# ViseraFPGA_v1_0.net
KiCad netlist of a schematic drawn in EAGLE
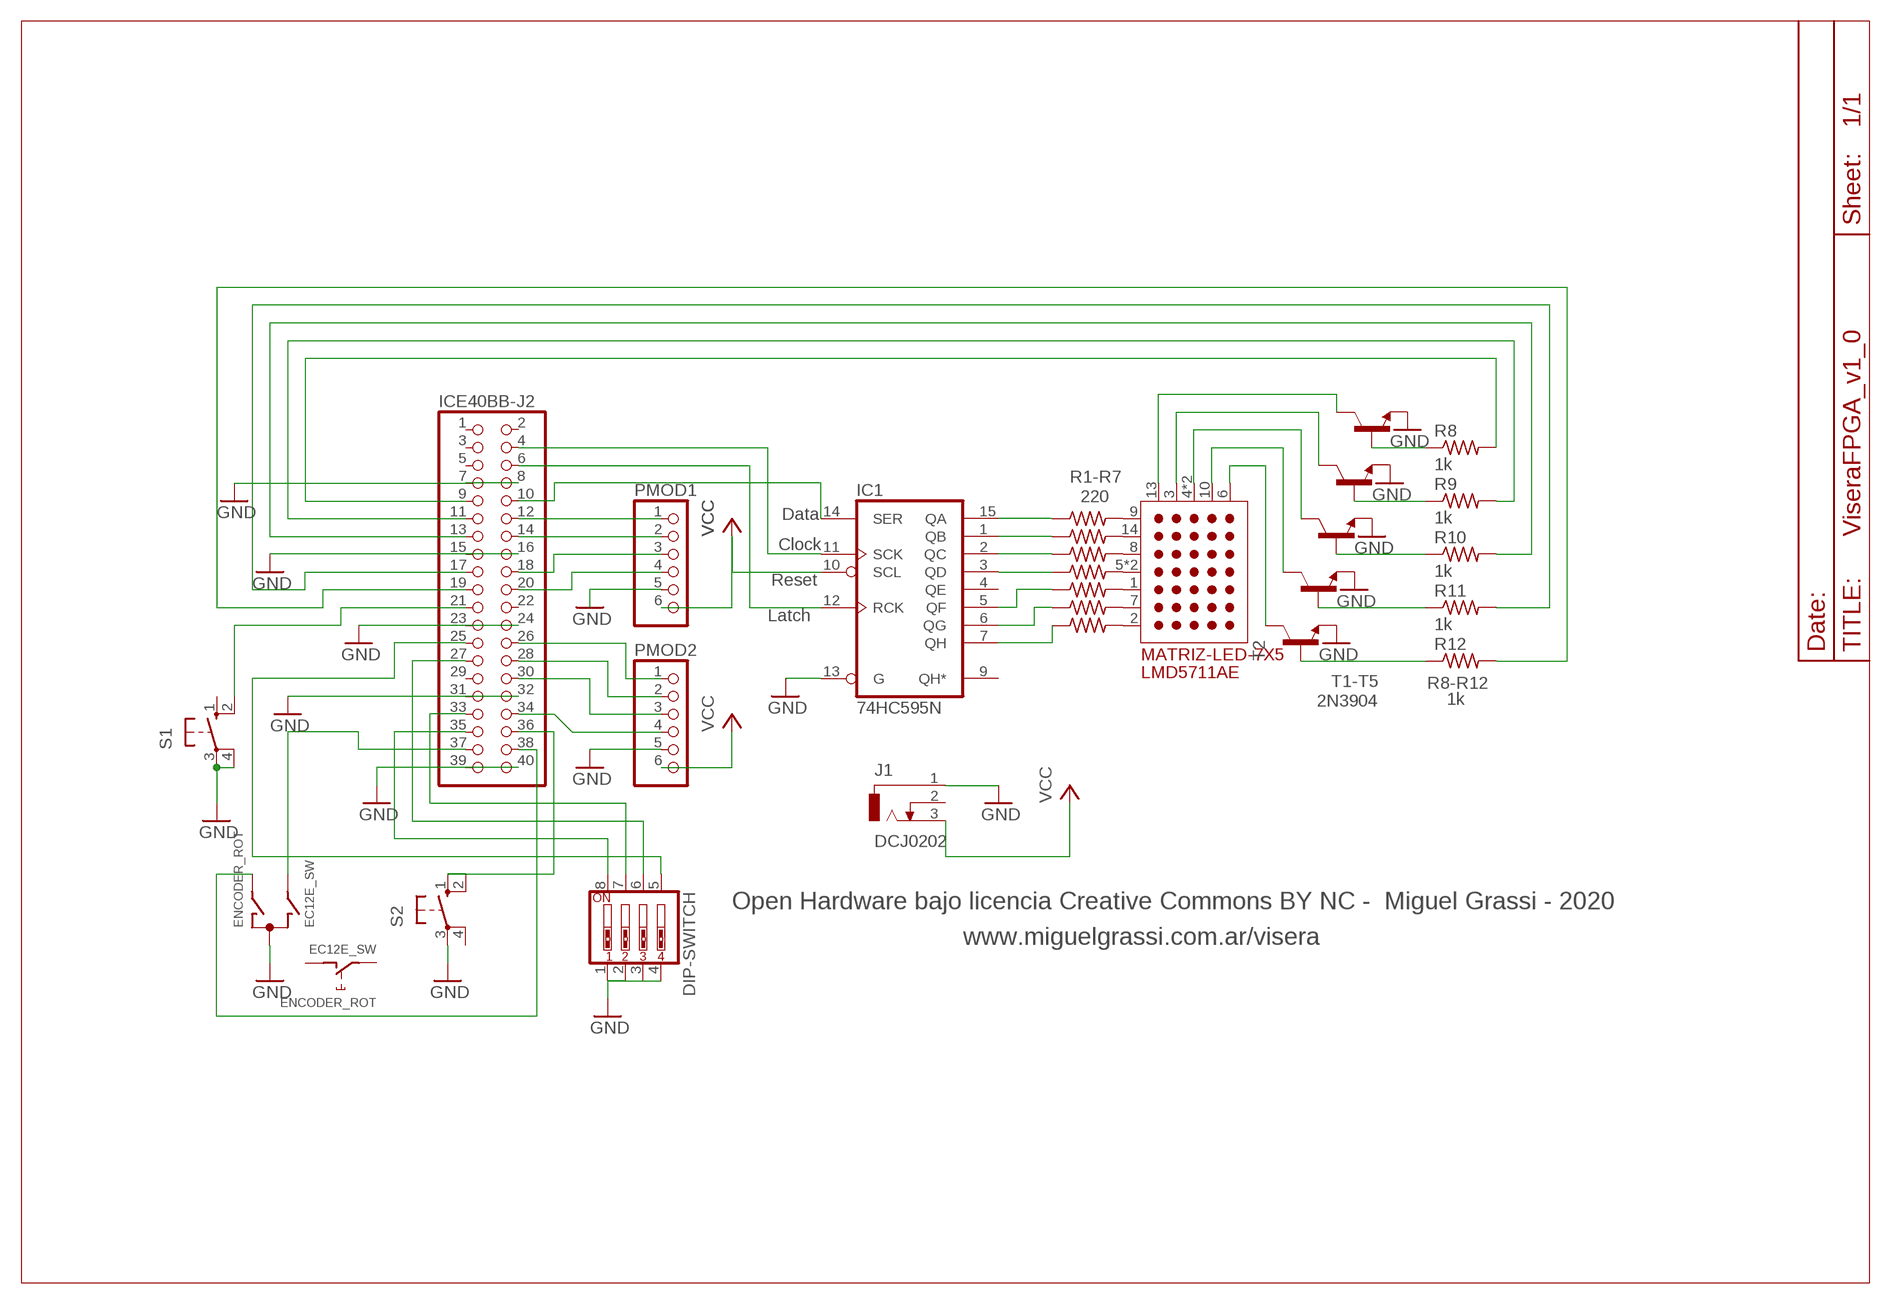
[diagram p0: schematic, sheet 1]

(export (version "E")
  (design (tool "Eeschema 10.0.6"))
  (components
    (comp (ref "DIP-SWITCH")
      (value "SW_DIP-4")
      (footprint "eagle-import:EDG-04")
      (libsource (lib "eagle-import") (part "SW_DIP-4"))
    )
    (comp (ref "ENCODER_ROT")
      (value "EC12E_SW")
      (footprint "eagle-import:ALPS_EC12E_SW")
      (fields (field (name "MPN") "EC12E2424407"))
      (libsource (lib "eagle-import") (part "EC12E_SW"))
    )
    (comp (ref "IC1")
      (value "74HC595N")
      (footprint "eagle-import:DIL16")
      (libsource (lib "eagle-import") (part "74595NHC"))
    )
    (comp (ref "ICE40BB-J2")
      (value "PINHD-2X20")
      (footprint "eagle-import:2X20")
      (libsource (lib "eagle-import") (part "PINHD-2X20"))
    )
    (comp (ref "J1")
      (value "DCJ0202")
      (footprint "eagle-import:DCJ0202")
      (libsource (lib "eagle-import") (part "DCJ0202"))
    )
    (comp (ref "MATRIZ-LED-7X5")
      (value "LMD5711AE")
      (footprint "eagle-import:LMD5711AE")
      (libsource (lib "eagle-import") (part "LMD5711AE"))
    )
    (comp (ref "PMOD1")
      (value "PINHD-1X6")
      (footprint "eagle-import:1X06")
      (libsource (lib "eagle-import") (part "PINHD-1X6"))
    )
    (comp (ref "PMOD2")
      (value "PINHD-1X6")
      (footprint "eagle-import:1X06")
      (libsource (lib "eagle-import") (part "PINHD-1X6"))
    )
    (comp (ref "R1")
      (value "220")
      (footprint "eagle-import:0207_7")
      (libsource (lib "eagle-import") (part "R-US_0207/7"))
    )
    (comp (ref "R2")
      (value "220")
      (footprint "eagle-import:0207_7")
      (libsource (lib "eagle-import") (part "R-US_0207/7"))
    )
    (comp (ref "R3")
      (value "220")
      (footprint "eagle-import:0207_7")
      (libsource (lib "eagle-import") (part "R-US_0207/7"))
    )
    (comp (ref "R4")
      (value "220")
      (footprint "eagle-import:0207_7")
      (libsource (lib "eagle-import") (part "R-US_0207/7"))
    )
    (comp (ref "R5")
      (value "220")
      (footprint "eagle-import:0207_7")
      (libsource (lib "eagle-import") (part "R-US_0207/7"))
    )
    (comp (ref "R6")
      (value "220")
      (footprint "eagle-import:0207_7")
      (libsource (lib "eagle-import") (part "R-US_0207/7"))
    )
    (comp (ref "R7")
      (value "220")
      (footprint "eagle-import:0207_7")
      (libsource (lib "eagle-import") (part "R-US_0207/7"))
    )
    (comp (ref "R8")
      (value "1k")
      (footprint "eagle-import:0207_7")
      (libsource (lib "eagle-import") (part "R-US_0207/7"))
    )
    (comp (ref "R9")
      (value "1k")
      (footprint "eagle-import:0207_7")
      (libsource (lib "eagle-import") (part "R-US_0207/7"))
    )
    (comp (ref "R10")
      (value "1k")
      (footprint "eagle-import:0207_7")
      (libsource (lib "eagle-import") (part "R-US_0207/7"))
    )
    (comp (ref "R11")
      (value "1k")
      (footprint "eagle-import:0207_7")
      (libsource (lib "eagle-import") (part "R-US_0207/7"))
    )
    (comp (ref "R12")
      (value "1k")
      (footprint "eagle-import:0207_7")
      (libsource (lib "eagle-import") (part "R-US_0207/7"))
    )
    (comp (ref "S1")
      (value "10-XX")
      (footprint "eagle-import:B3F-10XX")
      (fields (field (name "MPN") "B3F-1000"))
      (libsource (lib "eagle-import") (part "10-XX"))
    )
    (comp (ref "S2")
      (value "10-XX")
      (footprint "eagle-import:B3F-10XX")
      (fields (field (name "MPN") "B3F-1000"))
      (libsource (lib "eagle-import") (part "10-XX"))
    )
    (comp (ref "T1")
      (value "2N3904")
      (footprint "eagle-import:TO92")
      (libsource (lib "eagle-import") (part "2N3904"))
    )
    (comp (ref "T2")
      (value "2N3904")
      (footprint "eagle-import:TO92")
      (libsource (lib "eagle-import") (part "2N3904"))
    )
    (comp (ref "T3")
      (value "2N3904")
      (footprint "eagle-import:TO92")
      (libsource (lib "eagle-import") (part "2N3904"))
    )
    (comp (ref "T4")
      (value "2N3904")
      (footprint "eagle-import:TO92")
      (libsource (lib "eagle-import") (part "2N3904"))
    )
    (comp (ref "T5")
      (value "2N3904")
      (footprint "eagle-import:TO92")
      (libsource (lib "eagle-import") (part "2N3904"))
    )
  )
  (nets
    (net (code "1") (name "GND") (class "Default")
      (node (ref "DIP-SWITCH") (pin "1") (pinfunction "1_1") (pintype "passive"))
      (node (ref "DIP-SWITCH") (pin "2") (pinfunction "2_2") (pintype "passive"))
      (node (ref "DIP-SWITCH") (pin "3") (pinfunction "3_3") (pintype "passive"))
      (node (ref "DIP-SWITCH") (pin "4") (pinfunction "4_4") (pintype "passive"))
      (node (ref "ENCODER_ROT") (pin "C") (pinfunction "C_C") (pintype "passive"))
      (node (ref "IC1") (pin "13") (pinfunction "G_13") (pintype "input"))
      (node (ref "ICE40BB-J2") (pin "15") (pinfunction "15_15") (pintype "passive"))
      (node (ref "ICE40BB-J2") (pin "16") (pinfunction "16_16") (pintype "passive"))
      (node (ref "ICE40BB-J2") (pin "23") (pinfunction "23_23") (pintype "passive"))
      (node (ref "ICE40BB-J2") (pin "24") (pinfunction "24_24") (pintype "passive"))
      (node (ref "ICE40BB-J2") (pin "31") (pinfunction "31_31") (pintype "passive"))
      (node (ref "ICE40BB-J2") (pin "32") (pinfunction "32_32") (pintype "passive"))
      (node (ref "ICE40BB-J2") (pin "39") (pinfunction "39_39") (pintype "passive"))
      (node (ref "ICE40BB-J2") (pin "40") (pinfunction "40_40") (pintype "passive"))
      (node (ref "ICE40BB-J2") (pin "7") (pinfunction "7_7") (pintype "passive"))
      (node (ref "ICE40BB-J2") (pin "8") (pinfunction "8_8") (pintype "passive"))
      (node (ref "J1") (pin "1") (pinfunction "1_1") (pintype "passive"))
      (node (ref "PMOD1") (pin "5") (pinfunction "5_5") (pintype "passive"))
      (node (ref "PMOD2") (pin "5") (pinfunction "5_5") (pintype "passive"))
      (node (ref "S1") (pin "3") (pinfunction "P_3") (pintype "passive"))
      (node (ref "S1") (pin "4") (pinfunction "P1_4") (pintype "passive"))
      (node (ref "S2") (pin "3") (pinfunction "P_3") (pintype "passive"))
      (node (ref "T1") (pin "3") (pinfunction "E_3") (pintype "passive"))
      (node (ref "T2") (pin "3") (pinfunction "E_3") (pintype "passive"))
      (node (ref "T3") (pin "3") (pinfunction "E_3") (pintype "passive"))
      (node (ref "T4") (pin "3") (pinfunction "E_3") (pintype "passive"))
      (node (ref "T5") (pin "3") (pinfunction "E_3") (pintype "passive"))
    )
    (net (code "2") (name "Net-(DIP-SWITCH-Pad5)") (class "Default")
      (node (ref "DIP-SWITCH") (pin "5") (pinfunction "5_5") (pintype "passive"))
      (node (ref "ICE40BB-J2") (pin "25") (pinfunction "25_25") (pintype "passive"))
    )
    (net (code "3") (name "Net-(DIP-SWITCH-Pad6)") (class "Default")
      (node (ref "DIP-SWITCH") (pin "6") (pinfunction "6_6") (pintype "passive"))
      (node (ref "ICE40BB-J2") (pin "27") (pinfunction "27_27") (pintype "passive"))
    )
    (net (code "4") (name "Net-(DIP-SWITCH-Pad7)") (class "Default")
      (node (ref "DIP-SWITCH") (pin "7") (pinfunction "7_7") (pintype "passive"))
      (node (ref "ICE40BB-J2") (pin "33") (pinfunction "33_33") (pintype "passive"))
    )
    (net (code "5") (name "Net-(DIP-SWITCH-Pad8)") (class "Default")
      (node (ref "DIP-SWITCH") (pin "8") (pinfunction "8_8") (pintype "passive"))
      (node (ref "ICE40BB-J2") (pin "35") (pinfunction "35_35") (pintype "passive"))
    )
    (net (code "6") (name "Net-(ENCODER_ROT-PadA)") (class "Default")
      (node (ref "ENCODER_ROT") (pin "A") (pinfunction "A_A") (pintype "passive"))
      (node (ref "ICE40BB-J2") (pin "38") (pinfunction "38_38") (pintype "passive"))
    )
    (net (code "7") (name "Net-(ENCODER_ROT-PadB)") (class "Default")
      (node (ref "ENCODER_ROT") (pin "B") (pinfunction "B_B") (pintype "passive"))
      (node (ref "ICE40BB-J2") (pin "37") (pinfunction "37_37") (pintype "passive"))
    )
    (net (code "8") (name "Net-(IC1A-QA)") (class "Default")
      (node (ref "IC1") (pin "15") (pinfunction "QA_15") (pintype "tri_state"))
      (node (ref "R1") (pin "1") (pinfunction "1_1") (pintype "passive"))
    )
    (net (code "9") (name "Net-(IC1A-QB)") (class "Default")
      (node (ref "IC1") (pin "1") (pinfunction "QB_1") (pintype "tri_state"))
      (node (ref "R2") (pin "1") (pinfunction "1_1") (pintype "passive"))
    )
    (net (code "10") (name "Net-(IC1A-QC)") (class "Default")
      (node (ref "IC1") (pin "2") (pinfunction "QC_2") (pintype "tri_state"))
      (node (ref "R3") (pin "1") (pinfunction "1_1") (pintype "passive"))
    )
    (net (code "11") (name "Net-(IC1A-QD)") (class "Default")
      (node (ref "IC1") (pin "3") (pinfunction "QD_3") (pintype "tri_state"))
      (node (ref "R4") (pin "1") (pinfunction "1_1") (pintype "passive"))
    )
    (net (code "12") (name "Net-(IC1A-QF)") (class "Default")
      (node (ref "IC1") (pin "5") (pinfunction "QF_5") (pintype "tri_state"))
      (node (ref "R5") (pin "1") (pinfunction "1_1") (pintype "passive"))
    )
    (net (code "13") (name "Net-(IC1A-QG)") (class "Default")
      (node (ref "IC1") (pin "6") (pinfunction "QG_6") (pintype "tri_state"))
      (node (ref "R6") (pin "1") (pinfunction "1_1") (pintype "passive"))
    )
    (net (code "14") (name "Net-(IC1A-QH)") (class "Default")
      (node (ref "IC1") (pin "7") (pinfunction "QH_7") (pintype "tri_state"))
      (node (ref "R7") (pin "1") (pinfunction "1_1") (pintype "passive"))
    )
    (net (code "15") (name "Net-(IC1A-RCK)") (class "Default")
      (node (ref "IC1") (pin "12") (pinfunction "RCK_12") (pintype "input"))
      (node (ref "ICE40BB-J2") (pin "6") (pinfunction "6_6") (pintype "passive"))
    )
    (net (code "16") (name "Net-(IC1A-SCK)") (class "Default")
      (node (ref "IC1") (pin "11") (pinfunction "SCK_11") (pintype "input"))
      (node (ref "ICE40BB-J2") (pin "4") (pinfunction "4_4") (pintype "passive"))
    )
    (net (code "17") (name "Net-(IC1A-SER)") (class "Default")
      (node (ref "IC1") (pin "14") (pinfunction "SER_14") (pintype "input"))
      (node (ref "ICE40BB-J2") (pin "10") (pinfunction "10_10") (pintype "passive"))
    )
    (net (code "18") (name "Net-(ICE40BB-J2-Pad9)") (class "Default")
      (node (ref "ICE40BB-J2") (pin "9") (pinfunction "9_9") (pintype "passive"))
      (node (ref "R8") (pin "2") (pinfunction "2_2") (pintype "passive"))
    )
    (net (code "19") (name "Net-(ICE40BB-J2-Pad11)") (class "Default")
      (node (ref "ICE40BB-J2") (pin "11") (pinfunction "11_11") (pintype "passive"))
      (node (ref "R9") (pin "2") (pinfunction "2_2") (pintype "passive"))
    )
    (net (code "20") (name "Net-(ICE40BB-J2-Pad12)") (class "Default")
      (node (ref "ICE40BB-J2") (pin "12") (pinfunction "12_12") (pintype "passive"))
      (node (ref "PMOD1") (pin "1") (pinfunction "1_1") (pintype "passive"))
    )
    (net (code "21") (name "Net-(ICE40BB-J2-Pad13)") (class "Default")
      (node (ref "ICE40BB-J2") (pin "13") (pinfunction "13_13") (pintype "passive"))
      (node (ref "R10") (pin "2") (pinfunction "2_2") (pintype "passive"))
    )
    (net (code "22") (name "Net-(ICE40BB-J2-Pad14)") (class "Default")
      (node (ref "ICE40BB-J2") (pin "14") (pinfunction "14_14") (pintype "passive"))
      (node (ref "PMOD1") (pin "2") (pinfunction "2_2") (pintype "passive"))
    )
    (net (code "23") (name "Net-(ICE40BB-J2-Pad17)") (class "Default")
      (node (ref "ICE40BB-J2") (pin "17") (pinfunction "17_17") (pintype "passive"))
      (node (ref "R11") (pin "2") (pinfunction "2_2") (pintype "passive"))
    )
    (net (code "24") (name "Net-(ICE40BB-J2-Pad18)") (class "Default")
      (node (ref "ICE40BB-J2") (pin "18") (pinfunction "18_18") (pintype "passive"))
      (node (ref "PMOD1") (pin "3") (pinfunction "3_3") (pintype "passive"))
    )
    (net (code "25") (name "Net-(ICE40BB-J2-Pad19)") (class "Default")
      (node (ref "ICE40BB-J2") (pin "19") (pinfunction "19_19") (pintype "passive"))
      (node (ref "R12") (pin "2") (pinfunction "2_2") (pintype "passive"))
    )
    (net (code "26") (name "Net-(ICE40BB-J2-Pad20)") (class "Default")
      (node (ref "ICE40BB-J2") (pin "20") (pinfunction "20_20") (pintype "passive"))
      (node (ref "PMOD1") (pin "4") (pinfunction "4_4") (pintype "passive"))
    )
    (net (code "27") (name "Net-(ICE40BB-J2-Pad26)") (class "Default")
      (node (ref "ICE40BB-J2") (pin "26") (pinfunction "26_26") (pintype "passive"))
      (node (ref "PMOD2") (pin "1") (pinfunction "1_1") (pintype "passive"))
    )
    (net (code "28") (name "Net-(ICE40BB-J2-Pad28)") (class "Default")
      (node (ref "ICE40BB-J2") (pin "28") (pinfunction "28_28") (pintype "passive"))
      (node (ref "PMOD2") (pin "2") (pinfunction "2_2") (pintype "passive"))
    )
    (net (code "29") (name "Net-(ICE40BB-J2-Pad30)") (class "Default")
      (node (ref "ICE40BB-J2") (pin "30") (pinfunction "30_30") (pintype "passive"))
      (node (ref "PMOD2") (pin "3") (pinfunction "3_3") (pintype "passive"))
    )
    (net (code "30") (name "Net-(ICE40BB-J2-Pad34)") (class "Default")
      (node (ref "ICE40BB-J2") (pin "34") (pinfunction "34_34") (pintype "passive"))
      (node (ref "PMOD2") (pin "4") (pinfunction "4_4") (pintype "passive"))
    )
    (net (code "31") (name "Net-(MATRIZ-LED-7X5-C1)") (class "Default")
      (node (ref "MATRIZ-LED-7X5") (pin "13") (pinfunction "C1_13") (pintype "passive"))
      (node (ref "T5") (pin "1") (pinfunction "C_1") (pintype "passive"))
    )
    (net (code "32") (name "Net-(MATRIZ-LED-7X5-C2)") (class "Default")
      (node (ref "MATRIZ-LED-7X5") (pin "3") (pinfunction "C2_3") (pintype "passive"))
      (node (ref "T4") (pin "1") (pinfunction "C_1") (pintype "passive"))
    )
    (net (code "33") (name "Net-(MATRIZ-LED-7X5-C4)") (class "Default")
      (node (ref "MATRIZ-LED-7X5") (pin "10") (pinfunction "C4_10") (pintype "passive"))
      (node (ref "T2") (pin "1") (pinfunction "C_1") (pintype "passive"))
    )
    (net (code "34") (name "Net-(MATRIZ-LED-7X5-C5)") (class "Default")
      (node (ref "MATRIZ-LED-7X5") (pin "6") (pinfunction "C5_6") (pintype "passive"))
      (node (ref "T1") (pin "1") (pinfunction "C_1") (pintype "passive"))
    )
    (net (code "35") (name "Net-(MATRIZ-LED-7X5-R1)") (class "Default")
      (node (ref "MATRIZ-LED-7X5") (pin "9") (pinfunction "R1_9") (pintype "passive"))
      (node (ref "R1") (pin "2") (pinfunction "2_2") (pintype "passive"))
    )
    (net (code "36") (name "Net-(MATRIZ-LED-7X5-R2)") (class "Default")
      (node (ref "MATRIZ-LED-7X5") (pin "14") (pinfunction "R2_14") (pintype "passive"))
      (node (ref "R2") (pin "2") (pinfunction "2_2") (pintype "passive"))
    )
    (net (code "37") (name "Net-(MATRIZ-LED-7X5-R3)") (class "Default")
      (node (ref "MATRIZ-LED-7X5") (pin "8") (pinfunction "R3_8") (pintype "passive"))
      (node (ref "R3") (pin "2") (pinfunction "2_2") (pintype "passive"))
    )
    (net (code "38") (name "Net-(MATRIZ-LED-7X5-R4-Pad12)") (class "Default")
      (node (ref "MATRIZ-LED-7X5") (pin "12") (pinfunction "R4_12") (pintype "passive"))
      (node (ref "MATRIZ-LED-7X5") (pin "5") (pinfunction "R4_5") (pintype "passive"))
      (node (ref "R4") (pin "2") (pinfunction "2_2") (pintype "passive"))
    )
    (net (code "39") (name "Net-(MATRIZ-LED-7X5-R5)") (class "Default")
      (node (ref "MATRIZ-LED-7X5") (pin "1") (pinfunction "R5_1") (pintype "passive"))
      (node (ref "R5") (pin "2") (pinfunction "2_2") (pintype "passive"))
    )
    (net (code "40") (name "Net-(MATRIZ-LED-7X5-R6)") (class "Default")
      (node (ref "MATRIZ-LED-7X5") (pin "7") (pinfunction "R6_7") (pintype "passive"))
      (node (ref "R6") (pin "2") (pinfunction "2_2") (pintype "passive"))
    )
    (net (code "41") (name "Net-(MATRIZ-LED-7X5-R7)") (class "Default")
      (node (ref "MATRIZ-LED-7X5") (pin "2") (pinfunction "R7_2") (pintype "passive"))
      (node (ref "R7") (pin "2") (pinfunction "2_2") (pintype "passive"))
    )
    (net (code "42") (name "Net-(S1-S1)") (class "Default")
      (node (ref "ICE40BB-J2") (pin "21") (pinfunction "21_21") (pintype "passive"))
      (node (ref "S1") (pin "2") (pinfunction "S1_2") (pintype "passive"))
    )
    (net (code "43") (name "Net-(S2-S)") (class "Default")
      (node (ref "ICE40BB-J2") (pin "36") (pinfunction "36_36") (pintype "passive"))
      (node (ref "S2") (pin "1") (pinfunction "S_1") (pintype "passive"))
      (node (ref "S2") (pin "2") (pinfunction "S1_2") (pintype "passive"))
    )
    (net (code "44") (name "Net-(T1-B)") (class "Default")
      (node (ref "R12") (pin "1") (pinfunction "1_1") (pintype "passive"))
      (node (ref "T1") (pin "2") (pinfunction "B_2") (pintype "passive"))
    )
    (net (code "45") (name "Net-(T2-B)") (class "Default")
      (node (ref "R11") (pin "1") (pinfunction "1_1") (pintype "passive"))
      (node (ref "T2") (pin "2") (pinfunction "B_2") (pintype "passive"))
    )
    (net (code "46") (name "Net-(T3-B)") (class "Default")
      (node (ref "R10") (pin "1") (pinfunction "1_1") (pintype "passive"))
      (node (ref "T3") (pin "2") (pinfunction "B_2") (pintype "passive"))
    )
    (net (code "47") (name "Net-(T3-C)") (class "Default")
      (node (ref "MATRIZ-LED-7X5") (pin "11") (pinfunction "C3_11") (pintype "passive"))
      (node (ref "MATRIZ-LED-7X5") (pin "4") (pinfunction "C3_4") (pintype "passive"))
      (node (ref "T3") (pin "1") (pinfunction "C_1") (pintype "passive"))
    )
    (net (code "48") (name "Net-(T4-B)") (class "Default")
      (node (ref "R9") (pin "1") (pinfunction "1_1") (pintype "passive"))
      (node (ref "T4") (pin "2") (pinfunction "B_2") (pintype "passive"))
    )
    (net (code "49") (name "Net-(T5-B)") (class "Default")
      (node (ref "R8") (pin "1") (pinfunction "1_1") (pintype "passive"))
      (node (ref "T5") (pin "2") (pinfunction "B_2") (pintype "passive"))
    )
    (net (code "50") (name "VCC") (class "Default")
      (node (ref "IC1") (pin "10") (pinfunction "SCL_10") (pintype "input"))
      (node (ref "J1") (pin "3") (pinfunction "3_3") (pintype "passive"))
      (node (ref "PMOD1") (pin "6") (pinfunction "6_6") (pintype "passive"))
      (node (ref "PMOD2") (pin "6") (pinfunction "6_6") (pintype "passive"))
    )
    (net (code "51") (name "unconnected-(ENCODER_ROTB-1-PadD)") (class "Default")
      (node (ref "ENCODER_ROT") (pin "D") (pinfunction "1_D") (pintype "passive"))
    )
    (net (code "52") (name "unconnected-(ENCODER_ROTB-2-PadE)") (class "Default")
      (node (ref "ENCODER_ROT") (pin "E") (pinfunction "2_E") (pintype "passive"))
    )
    (net (code "53") (name "unconnected-(IC1A-QE-Pad4)") (class "Default")
      (node (ref "IC1") (pin "4") (pinfunction "QE_4") (pintype "tri_state"))
    )
    (net (code "54") (name "unconnected-(IC1A-QH*-Pad9)") (class "Default")
      (node (ref "IC1") (pin "9") (pinfunction "QH*_9") (pintype "tri_state"))
    )
    (net (code "55") (name "unconnected-(ICE40BB-J2-Pad1)") (class "Default")
      (node (ref "ICE40BB-J2") (pin "1") (pinfunction "1_1") (pintype "passive"))
    )
    (net (code "56") (name "unconnected-(ICE40BB-J2-Pad2)") (class "Default")
      (node (ref "ICE40BB-J2") (pin "2") (pinfunction "2_2") (pintype "passive"))
    )
    (net (code "57") (name "unconnected-(ICE40BB-J2-Pad3)") (class "Default")
      (node (ref "ICE40BB-J2") (pin "3") (pinfunction "3_3") (pintype "passive"))
    )
    (net (code "58") (name "unconnected-(ICE40BB-J2-Pad5)") (class "Default")
      (node (ref "ICE40BB-J2") (pin "5") (pinfunction "5_5") (pintype "passive"))
    )
    (net (code "59") (name "unconnected-(ICE40BB-J2-Pad22)") (class "Default")
      (node (ref "ICE40BB-J2") (pin "22") (pinfunction "22_22") (pintype "passive"))
    )
    (net (code "60") (name "unconnected-(ICE40BB-J2-Pad29)") (class "Default")
      (node (ref "ICE40BB-J2") (pin "29") (pinfunction "29_29") (pintype "passive"))
    )
    (net (code "61") (name "unconnected-(J1-Pad2)") (class "Default")
      (node (ref "J1") (pin "2") (pinfunction "2_2") (pintype "passive"))
    )
    (net (code "62") (name "unconnected-(S1-S-Pad1)") (class "Default")
      (node (ref "S1") (pin "1") (pinfunction "S_1") (pintype "passive"))
    )
    (net (code "63") (name "unconnected-(S2-P1-Pad4)") (class "Default")
      (node (ref "S2") (pin "4") (pinfunction "P1_4") (pintype "passive"))
    )
  )
)
